# ANTENNE.net
KiCad netlist of a schematic drawn in Altium Designer
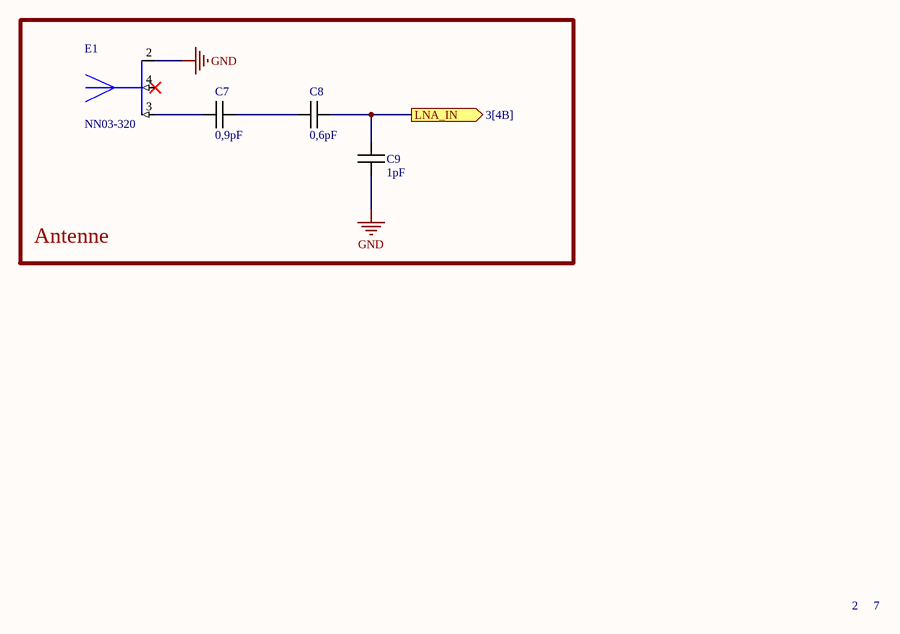
[diagram p0: ANTENNE.SchDoc]

(export (version "E")
  (design (tool "Eeschema 10.0.6"))
  (components
    (comp (ref "C7")
      (value "0,9pF")
      (footprint "CAPC1005X06N")
      (libsource (lib "SCHLibrary") (part "Capacitor"))
    )
    (comp (ref "C8")
      (value "0,6pF")
      (footprint "CAPC1005X06N")
      (libsource (lib "SCHLibrary") (part "Capacitor"))
    )
    (comp (ref "C9")
      (value "1pF")
      (footprint "CAPC1005X06N")
      (libsource (lib "SCHLibrary") (part "Capacitor"))
    )
    (comp (ref "E1")
      (value "NN03-320")
      (footprint "XCVR_NN03-320")
      (fields (field (name "MOUSER PART NUMBER") "128-NN03-320"))
      (libsource (lib "SCHLibrary") (part "NN03-320"))
    )
  )
  (nets
    (net (code "1") (name "/LNA_IN") (class "Default")
      (node (ref "C8") (pin "2") (pinfunction "2_2") (pintype "passive"))
      (node (ref "C9") (pin "2") (pinfunction "2_2") (pintype "passive"))
    )
    (net (code "2") (name "GND") (class "Default")
      (node (ref "C9") (pin "1") (pinfunction "1_1") (pintype "passive"))
      (node (ref "E1") (pin "2") (pinfunction "GROUND_2") (pintype "power_in"))
    )
    (net (code "3") (name "Net-(C7-Pad2)") (class "Default")
      (node (ref "C7") (pin "2") (pinfunction "2_2") (pintype "passive"))
      (node (ref "C8") (pin "1") (pinfunction "1_1") (pintype "passive"))
    )
    (net (code "4") (name "Net-(E1-FEED_BLUETOOTH)") (class "Default")
      (node (ref "C7") (pin "1") (pinfunction "1_1") (pintype "passive"))
      (node (ref "E1") (pin "3") (pinfunction "FEED_BLUETOOTH_3") (pintype "input"))
    )
    (net (code "5") (name "unconnected-(E1-FEED_GNSS-Pad4)") (class "Default")
      (node (ref "E1") (pin "4") (pinfunction "FEED_GNSS_4") (pintype "input+no_connect"))
    )
  )
)
